# Habit-Reformer.net
KiCad netlist of a schematic drawn in EAGLE
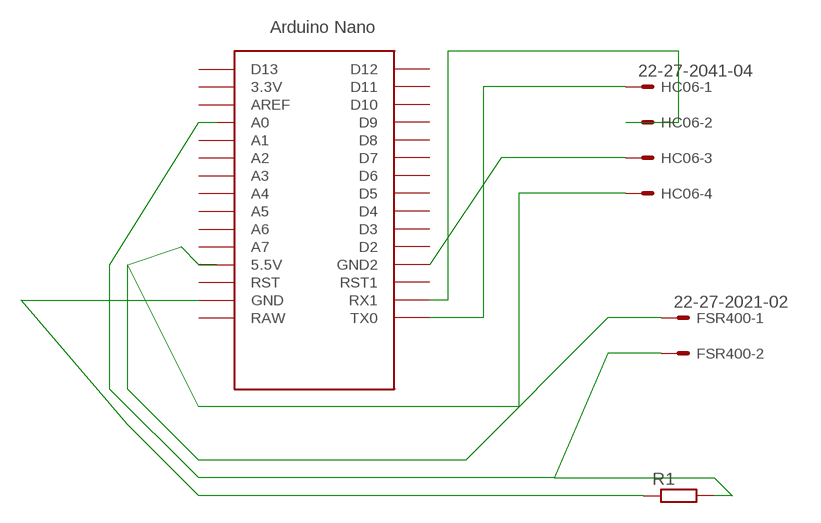
[diagram p0: schematic, sheet 1]

(export (version "E")
  (design (tool "Eeschema 10.0.6"))
  (components
    (comp (ref "FSR400")
      (value "22-27-2021-02")
      (footprint "eagle-import:6410-02")
      (libsource (lib "eagle-import") (part "22-?-0227-2021"))
    )
    (comp (ref "HC06")
      (value "22-27-2041-04")
      (footprint "eagle-import:6410-04")
      (libsource (lib "eagle-import") (part "22-?-0427-2041"))
    )
    (comp (ref "R1")
      (value "R-EU_0204/7")
      (footprint "eagle-import:0204_7")
      (libsource (lib "eagle-import") (part "R-EU_0204/7"))
    )
    (comp (ref "U$1")
      (value "NANO")
      (footprint "eagle-import:NANO")
      (libsource (lib "eagle-import") (part "NANO"))
    )
  )
  (nets
    (net (code "1") (name "Net-(FSR400A-S)") (class "Default")
      (node (ref "FSR400") (pin "1") (pinfunction "S_1") (pintype "passive"))
      (node (ref "HC06") (pin "4") (pinfunction "S_4") (pintype "passive"))
      (node (ref "U$1") (pin "5V") (pinfunction "5.5V_5V") (pintype "bidirectional"))
    )
    (net (code "2") (name "Net-(FSR400B-S)") (class "Default")
      (node (ref "FSR400") (pin "2") (pinfunction "S_2") (pintype "passive"))
      (node (ref "R1") (pin "2") (pinfunction "2_2") (pintype "passive"))
      (node (ref "U$1") (pin "A0") (pinfunction "A0_A0") (pintype "bidirectional"))
    )
    (net (code "3") (name "Net-(HC06A-S)") (class "Default")
      (node (ref "HC06") (pin "1") (pinfunction "S_1") (pintype "passive"))
      (node (ref "U$1") (pin "TX0") (pinfunction "TX0_TX0") (pintype "bidirectional"))
    )
    (net (code "4") (name "Net-(HC06B-S)") (class "Default")
      (node (ref "HC06") (pin "2") (pinfunction "S_2") (pintype "passive"))
      (node (ref "U$1") (pin "RX1") (pinfunction "RX1_RX1") (pintype "bidirectional"))
    )
    (net (code "5") (name "Net-(HC06C-S)") (class "Default")
      (node (ref "HC06") (pin "3") (pinfunction "S_3") (pintype "passive"))
      (node (ref "U$1") (pin "GND1") (pinfunction "GND2_GND1") (pintype "bidirectional"))
    )
    (net (code "6") (name "Net-(R1-Pad1)") (class "Default")
      (node (ref "R1") (pin "1") (pinfunction "1_1") (pintype "passive"))
      (node (ref "U$1") (pin "GND") (pinfunction "GND_GND") (pintype "bidirectional"))
    )
    (net (code "7") (name "unconnected-(U$1-Pad3.3V)") (class "Default")
      (node (ref "U$1") (pin "3.3V") (pinfunction "3.3V_3.3V") (pintype "bidirectional"))
    )
    (net (code "8") (name "unconnected-(U$1-PadA1)") (class "Default")
      (node (ref "U$1") (pin "A1") (pinfunction "A1_A1") (pintype "bidirectional"))
    )
    (net (code "9") (name "unconnected-(U$1-PadA2)") (class "Default")
      (node (ref "U$1") (pin "A2") (pinfunction "A2_A2") (pintype "bidirectional"))
    )
    (net (code "10") (name "unconnected-(U$1-PadA3)") (class "Default")
      (node (ref "U$1") (pin "A3") (pinfunction "A3_A3") (pintype "bidirectional"))
    )
    (net (code "11") (name "unconnected-(U$1-PadA4)") (class "Default")
      (node (ref "U$1") (pin "A4") (pinfunction "A4_A4") (pintype "bidirectional"))
    )
    (net (code "12") (name "unconnected-(U$1-PadA5)") (class "Default")
      (node (ref "U$1") (pin "A5") (pinfunction "A5_A5") (pintype "bidirectional"))
    )
    (net (code "13") (name "unconnected-(U$1-PadA6)") (class "Default")
      (node (ref "U$1") (pin "A6") (pinfunction "A6_A6") (pintype "bidirectional"))
    )
    (net (code "14") (name "unconnected-(U$1-PadA7)") (class "Default")
      (node (ref "U$1") (pin "A7") (pinfunction "A7_A7") (pintype "bidirectional"))
    )
    (net (code "15") (name "unconnected-(U$1-PadAREF)") (class "Default")
      (node (ref "U$1") (pin "AREF") (pinfunction "AREF_AREF") (pintype "bidirectional"))
    )
    (net (code "16") (name "unconnected-(U$1-PadD2)") (class "Default")
      (node (ref "U$1") (pin "D2") (pinfunction "D2_D2") (pintype "bidirectional"))
    )
    (net (code "17") (name "unconnected-(U$1-PadD3)") (class "Default")
      (node (ref "U$1") (pin "D3") (pinfunction "D3_D3") (pintype "bidirectional"))
    )
    (net (code "18") (name "unconnected-(U$1-PadD4)") (class "Default")
      (node (ref "U$1") (pin "D4") (pinfunction "D4_D4") (pintype "bidirectional"))
    )
    (net (code "19") (name "unconnected-(U$1-PadD5)") (class "Default")
      (node (ref "U$1") (pin "D5") (pinfunction "D5_D5") (pintype "bidirectional"))
    )
    (net (code "20") (name "unconnected-(U$1-PadD6)") (class "Default")
      (node (ref "U$1") (pin "D6") (pinfunction "D6_D6") (pintype "bidirectional"))
    )
    (net (code "21") (name "unconnected-(U$1-PadD7)") (class "Default")
      (node (ref "U$1") (pin "D7") (pinfunction "D7_D7") (pintype "bidirectional"))
    )
    (net (code "22") (name "unconnected-(U$1-PadD8)") (class "Default")
      (node (ref "U$1") (pin "D8") (pinfunction "D8_D8") (pintype "bidirectional"))
    )
    (net (code "23") (name "unconnected-(U$1-PadD9)") (class "Default")
      (node (ref "U$1") (pin "D9") (pinfunction "D9_D9") (pintype "bidirectional"))
    )
    (net (code "24") (name "unconnected-(U$1-PadD10)") (class "Default")
      (node (ref "U$1") (pin "D10") (pinfunction "D10_D10") (pintype "bidirectional"))
    )
    (net (code "25") (name "unconnected-(U$1-PadD11)") (class "Default")
      (node (ref "U$1") (pin "D11") (pinfunction "D11_D11") (pintype "bidirectional"))
    )
    (net (code "26") (name "unconnected-(U$1-PadD12)") (class "Default")
      (node (ref "U$1") (pin "D12") (pinfunction "D12_D12") (pintype "bidirectional"))
    )
    (net (code "27") (name "unconnected-(U$1-PadD13)") (class "Default")
      (node (ref "U$1") (pin "D13") (pinfunction "D13_D13") (pintype "bidirectional"))
    )
    (net (code "28") (name "unconnected-(U$1-PadICSP1)") (class "Default")
      (node (ref "U$1") (pin "ICSP1") (pinfunction "ICSP1_ICSP1") (pintype "bidirectional"))
    )
    (net (code "29") (name "unconnected-(U$1-PadICSP2)") (class "Default")
      (node (ref "U$1") (pin "ICSP2") (pinfunction "ICSP2_ICSP2") (pintype "bidirectional"))
    )
    (net (code "30") (name "unconnected-(U$1-PadICSP3)") (class "Default")
      (node (ref "U$1") (pin "ICSP3") (pinfunction "ICSP3_ICSP3") (pintype "bidirectional"))
    )
    (net (code "31") (name "unconnected-(U$1-PadICSP4)") (class "Default")
      (node (ref "U$1") (pin "ICSP4") (pinfunction "ICSP4_ICSP4") (pintype "bidirectional"))
    )
    (net (code "32") (name "unconnected-(U$1-PadICSP5)") (class "Default")
      (node (ref "U$1") (pin "ICSP5") (pinfunction "ICSP5_ICSP5") (pintype "bidirectional"))
    )
    (net (code "33") (name "unconnected-(U$1-PadICSP6)") (class "Default")
      (node (ref "U$1") (pin "ICSP6") (pinfunction "ICSP6_ICSP6") (pintype "bidirectional"))
    )
    (net (code "34") (name "unconnected-(U$1-PadRAW)") (class "Default")
      (node (ref "U$1") (pin "RAW") (pinfunction "RAW_RAW") (pintype "bidirectional"))
    )
    (net (code "35") (name "unconnected-(U$1-PadRST)") (class "Default")
      (node (ref "U$1") (pin "RST") (pinfunction "RST_RST") (pintype "bidirectional"))
    )
    (net (code "36") (name "unconnected-(U$1-PadRST1)") (class "Default")
      (node (ref "U$1") (pin "RST1") (pinfunction "RST1_RST1") (pintype "bidirectional"))
    )
  )
)
